# Humidorium.net
KiCad netlist of a schematic drawn in EAGLE
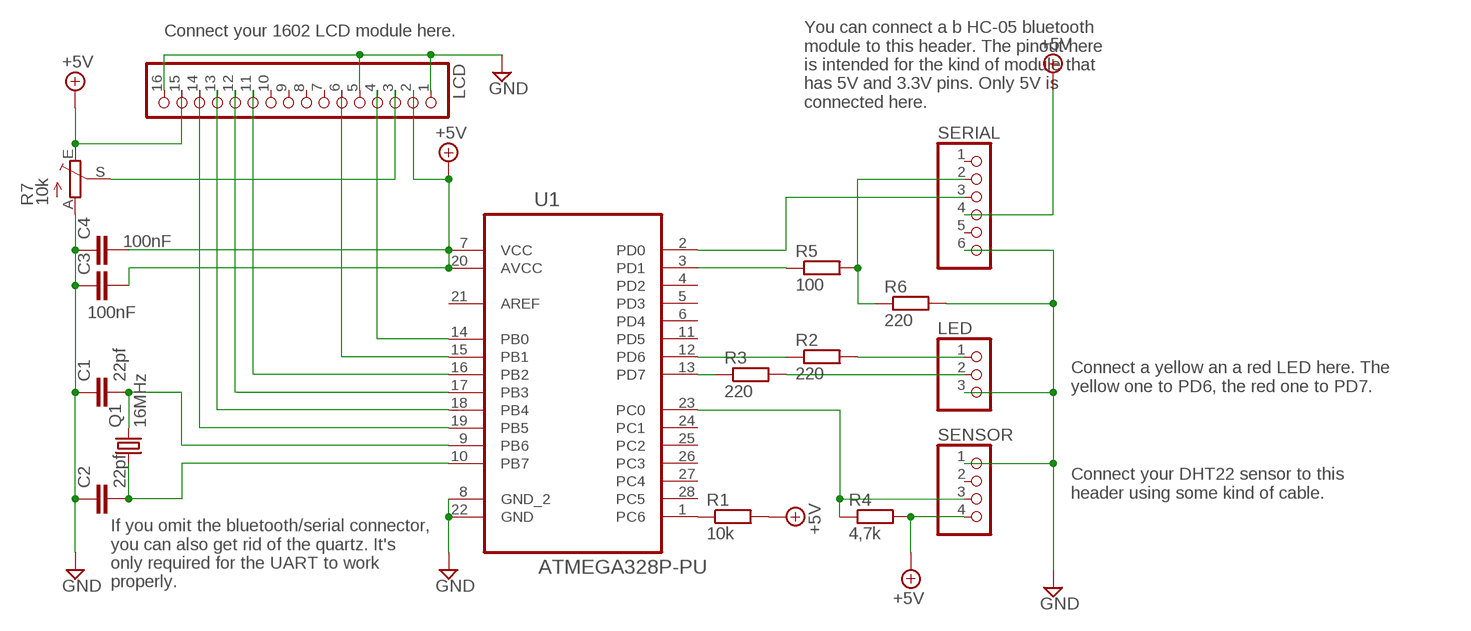
[diagram p0: schematic, sheet 1]

(export (version "E")
  (design (tool "Eeschema 10.0.6"))
  (components
    (comp (ref "C1")
      (value "22pf")
      (footprint "eagle-import:C025-024X044")
      (libsource (lib "eagle-import") (part "C-EU025-024X044"))
    )
    (comp (ref "C2")
      (value "22pf")
      (footprint "eagle-import:C025-024X044")
      (libsource (lib "eagle-import") (part "C-EU025-024X044"))
    )
    (comp (ref "C3")
      (value "100nF")
      (footprint "eagle-import:C025-024X044")
      (libsource (lib "eagle-import") (part "C-EU025-024X044"))
    )
    (comp (ref "C4")
      (value "100nF")
      (footprint "eagle-import:C025-024X044")
      (libsource (lib "eagle-import") (part "C-EU025-024X044"))
    )
    (comp (ref "LCD")
      (value "PINHD-1X16")
      (footprint "eagle-import:1X16")
      (libsource (lib "eagle-import") (part "PINHD-1X16"))
    )
    (comp (ref "LED")
      (value "PINHD-1X3")
      (footprint "eagle-import:1X03")
      (libsource (lib "eagle-import") (part "PINHD-1X3"))
    )
    (comp (ref "Q1")
      (value "16MHz")
      (footprint "eagle-import:HC33U-V")
      (libsource (lib "eagle-import") (part "CRYSTALHC33U-V"))
    )
    (comp (ref "R1")
      (value "10k")
      (footprint "eagle-import:0204V")
      (libsource (lib "eagle-import") (part "R-EU_0204/2V"))
    )
    (comp (ref "R2")
      (value "220")
      (footprint "eagle-import:0204_7")
      (libsource (lib "eagle-import") (part "R-EU_0204/7"))
    )
    (comp (ref "R3")
      (value "220")
      (footprint "eagle-import:0204_7")
      (libsource (lib "eagle-import") (part "R-EU_0204/7"))
    )
    (comp (ref "R4")
      (value "4,7k")
      (footprint "eagle-import:0204_7")
      (libsource (lib "eagle-import") (part "R-EU_0204/7"))
    )
    (comp (ref "R5")
      (value "100")
      (footprint "eagle-import:0204_7")
      (libsource (lib "eagle-import") (part "R-EU_0204/7"))
    )
    (comp (ref "R6")
      (value "220")
      (footprint "eagle-import:0204_7")
      (libsource (lib "eagle-import") (part "R-EU_0204/7"))
    )
    (comp (ref "R7")
      (value "10k")
      (footprint "eagle-import:B25P")
      (libsource (lib "eagle-import") (part "TRIM_EU-B25P"))
    )
    (comp (ref "SENSOR")
      (value "PINHD-1X4")
      (footprint "eagle-import:1X04")
      (libsource (lib "eagle-import") (part "PINHD-1X4"))
    )
    (comp (ref "SERIAL")
      (value "PINHD-1X6")
      (footprint "eagle-import:1X06")
      (libsource (lib "eagle-import") (part "PINHD-1X6"))
    )
    (comp (ref "U1")
      (value "ATMEGA328P-PU")
      (footprint "eagle-import:DIP254P762X457-28")
      (libsource (lib "eagle-import") (part "ATMEGA328P-PU"))
    )
  )
  (nets
    (net (code "1") (name "+5V") (class "Default")
      (node (ref "C3") (pin "2") (pinfunction "2_2") (pintype "passive"))
      (node (ref "C4") (pin "2") (pinfunction "2_2") (pintype "passive"))
      (node (ref "LCD") (pin "15") (pinfunction "15_15") (pintype "passive"))
      (node (ref "LCD") (pin "2") (pinfunction "2_2") (pintype "passive"))
      (node (ref "R1") (pin "2") (pinfunction "2_2") (pintype "passive"))
      (node (ref "R4") (pin "2") (pinfunction "2_2") (pintype "passive"))
      (node (ref "R7") (pin "E") (pinfunction "E_E") (pintype "passive"))
      (node (ref "SENSOR") (pin "4") (pinfunction "4_4") (pintype "passive"))
      (node (ref "SERIAL") (pin "4") (pinfunction "4_4") (pintype "passive"))
      (node (ref "U1") (pin "20") (pinfunction "AVCC_20") (pintype "power_in"))
      (node (ref "U1") (pin "7") (pinfunction "VCC_7") (pintype "power_in"))
    )
    (net (code "2") (name "GND") (class "Default")
      (node (ref "C1") (pin "1") (pinfunction "1_1") (pintype "passive"))
      (node (ref "C2") (pin "1") (pinfunction "1_1") (pintype "passive"))
      (node (ref "C3") (pin "1") (pinfunction "1_1") (pintype "passive"))
      (node (ref "C4") (pin "1") (pinfunction "1_1") (pintype "passive"))
      (node (ref "LCD") (pin "1") (pinfunction "1_1") (pintype "passive"))
      (node (ref "LCD") (pin "16") (pinfunction "16_16") (pintype "passive"))
      (node (ref "LCD") (pin "5") (pinfunction "5_5") (pintype "passive"))
      (node (ref "LED") (pin "3") (pinfunction "3_3") (pintype "passive"))
      (node (ref "R6") (pin "2") (pinfunction "2_2") (pintype "passive"))
      (node (ref "R7") (pin "A") (pinfunction "A_A") (pintype "passive"))
      (node (ref "SENSOR") (pin "1") (pinfunction "1_1") (pintype "passive"))
      (node (ref "SERIAL") (pin "6") (pinfunction "6_6") (pintype "passive"))
      (node (ref "U1") (pin "22") (pinfunction "GND_22") (pintype "passive"))
      (node (ref "U1") (pin "8") (pinfunction "GND_2_8") (pintype "passive"))
    )
    (net (code "3") (name "Net-(LCD-Pad3)") (class "Default")
      (node (ref "LCD") (pin "3") (pinfunction "3_3") (pintype "passive"))
      (node (ref "R7") (pin "S") (pinfunction "S_S") (pintype "passive"))
    )
    (net (code "4") (name "Net-(LED-Pad1)") (class "Default")
      (node (ref "LED") (pin "1") (pinfunction "1_1") (pintype "passive"))
      (node (ref "R2") (pin "2") (pinfunction "2_2") (pintype "passive"))
    )
    (net (code "5") (name "Net-(LED-Pad2)") (class "Default")
      (node (ref "LED") (pin "2") (pinfunction "2_2") (pintype "passive"))
      (node (ref "R3") (pin "2") (pinfunction "2_2") (pintype "passive"))
    )
    (net (code "6") (name "Net-(R5-Pad2)") (class "Default")
      (node (ref "R5") (pin "2") (pinfunction "2_2") (pintype "passive"))
      (node (ref "R6") (pin "1") (pinfunction "1_1") (pintype "passive"))
      (node (ref "SERIAL") (pin "2") (pinfunction "2_2") (pintype "passive"))
    )
    (net (code "7") (name "Net-(U1-PB0)") (class "Default")
      (node (ref "LCD") (pin "4") (pinfunction "4_4") (pintype "passive"))
      (node (ref "U1") (pin "14") (pinfunction "PB0_14") (pintype "bidirectional"))
    )
    (net (code "8") (name "Net-(U1-PB1)") (class "Default")
      (node (ref "LCD") (pin "6") (pinfunction "6_6") (pintype "passive"))
      (node (ref "U1") (pin "15") (pinfunction "PB1_15") (pintype "bidirectional"))
    )
    (net (code "9") (name "Net-(U1-PB2)") (class "Default")
      (node (ref "LCD") (pin "11") (pinfunction "11_11") (pintype "passive"))
      (node (ref "U1") (pin "16") (pinfunction "PB2_16") (pintype "bidirectional"))
    )
    (net (code "10") (name "Net-(U1-PB3)") (class "Default")
      (node (ref "LCD") (pin "12") (pinfunction "12_12") (pintype "passive"))
      (node (ref "U1") (pin "17") (pinfunction "PB3_17") (pintype "bidirectional"))
    )
    (net (code "11") (name "Net-(U1-PB4)") (class "Default")
      (node (ref "LCD") (pin "13") (pinfunction "13_13") (pintype "passive"))
      (node (ref "U1") (pin "18") (pinfunction "PB4_18") (pintype "bidirectional"))
    )
    (net (code "12") (name "Net-(U1-PB5)") (class "Default")
      (node (ref "LCD") (pin "14") (pinfunction "14_14") (pintype "passive"))
      (node (ref "U1") (pin "19") (pinfunction "PB5_19") (pintype "bidirectional"))
    )
    (net (code "13") (name "Net-(U1-PB6)") (class "Default")
      (node (ref "C1") (pin "2") (pinfunction "2_2") (pintype "passive"))
      (node (ref "Q1") (pin "2") (pinfunction "2_2") (pintype "passive"))
      (node (ref "U1") (pin "9") (pinfunction "PB6_9") (pintype "bidirectional"))
    )
    (net (code "14") (name "Net-(U1-PB7)") (class "Default")
      (node (ref "C2") (pin "2") (pinfunction "2_2") (pintype "passive"))
      (node (ref "Q1") (pin "1") (pinfunction "1_1") (pintype "passive"))
      (node (ref "U1") (pin "10") (pinfunction "PB7_10") (pintype "bidirectional"))
    )
    (net (code "15") (name "Net-(U1-PC0)") (class "Default")
      (node (ref "R4") (pin "1") (pinfunction "1_1") (pintype "passive"))
      (node (ref "SENSOR") (pin "3") (pinfunction "3_3") (pintype "passive"))
      (node (ref "U1") (pin "23") (pinfunction "PC0_23") (pintype "bidirectional"))
    )
    (net (code "16") (name "Net-(U1-PC6)") (class "Default")
      (node (ref "R1") (pin "1") (pinfunction "1_1") (pintype "passive"))
      (node (ref "U1") (pin "1") (pinfunction "PC6_1") (pintype "bidirectional"))
    )
    (net (code "17") (name "Net-(U1-PD0)") (class "Default")
      (node (ref "SERIAL") (pin "3") (pinfunction "3_3") (pintype "passive"))
      (node (ref "U1") (pin "2") (pinfunction "PD0_2") (pintype "bidirectional"))
    )
    (net (code "18") (name "Net-(U1-PD1)") (class "Default")
      (node (ref "R5") (pin "1") (pinfunction "1_1") (pintype "passive"))
      (node (ref "U1") (pin "3") (pinfunction "PD1_3") (pintype "bidirectional"))
    )
    (net (code "19") (name "Net-(U1-PD6)") (class "Default")
      (node (ref "R2") (pin "1") (pinfunction "1_1") (pintype "passive"))
      (node (ref "U1") (pin "12") (pinfunction "PD6_12") (pintype "bidirectional"))
    )
    (net (code "20") (name "Net-(U1-PD7)") (class "Default")
      (node (ref "R3") (pin "1") (pinfunction "1_1") (pintype "passive"))
      (node (ref "U1") (pin "13") (pinfunction "PD7_13") (pintype "bidirectional"))
    )
    (net (code "21") (name "unconnected-(LCD-Pad7)") (class "Default")
      (node (ref "LCD") (pin "7") (pinfunction "7_7") (pintype "passive"))
    )
    (net (code "22") (name "unconnected-(LCD-Pad8)") (class "Default")
      (node (ref "LCD") (pin "8") (pinfunction "8_8") (pintype "passive"))
    )
    (net (code "23") (name "unconnected-(LCD-Pad9)") (class "Default")
      (node (ref "LCD") (pin "9") (pinfunction "9_9") (pintype "passive"))
    )
    (net (code "24") (name "unconnected-(LCD-Pad10)") (class "Default")
      (node (ref "LCD") (pin "10") (pinfunction "10_10") (pintype "passive"))
    )
    (net (code "25") (name "unconnected-(SENSOR-Pad2)") (class "Default")
      (node (ref "SENSOR") (pin "2") (pinfunction "2_2") (pintype "passive"))
    )
    (net (code "26") (name "unconnected-(SERIAL-Pad1)") (class "Default")
      (node (ref "SERIAL") (pin "1") (pinfunction "1_1") (pintype "passive"))
    )
    (net (code "27") (name "unconnected-(SERIAL-Pad5)") (class "Default")
      (node (ref "SERIAL") (pin "5") (pinfunction "5_5") (pintype "passive"))
    )
    (net (code "28") (name "unconnected-(U1-AREF-Pad21)") (class "Default")
      (node (ref "U1") (pin "21") (pinfunction "AREF_21") (pintype "input"))
    )
    (net (code "29") (name "unconnected-(U1-PC1-Pad24)") (class "Default")
      (node (ref "U1") (pin "24") (pinfunction "PC1_24") (pintype "bidirectional"))
    )
    (net (code "30") (name "unconnected-(U1-PC2-Pad25)") (class "Default")
      (node (ref "U1") (pin "25") (pinfunction "PC2_25") (pintype "bidirectional"))
    )
    (net (code "31") (name "unconnected-(U1-PC3-Pad26)") (class "Default")
      (node (ref "U1") (pin "26") (pinfunction "PC3_26") (pintype "bidirectional"))
    )
    (net (code "32") (name "unconnected-(U1-PC4-Pad27)") (class "Default")
      (node (ref "U1") (pin "27") (pinfunction "PC4_27") (pintype "bidirectional"))
    )
    (net (code "33") (name "unconnected-(U1-PC5-Pad28)") (class "Default")
      (node (ref "U1") (pin "28") (pinfunction "PC5_28") (pintype "bidirectional"))
    )
    (net (code "34") (name "unconnected-(U1-PD2-Pad4)") (class "Default")
      (node (ref "U1") (pin "4") (pinfunction "PD2_4") (pintype "bidirectional"))
    )
    (net (code "35") (name "unconnected-(U1-PD3-Pad5)") (class "Default")
      (node (ref "U1") (pin "5") (pinfunction "PD3_5") (pintype "bidirectional"))
    )
    (net (code "36") (name "unconnected-(U1-PD4-Pad6)") (class "Default")
      (node (ref "U1") (pin "6") (pinfunction "PD4_6") (pintype "bidirectional"))
    )
    (net (code "37") (name "unconnected-(U1-PD5-Pad11)") (class "Default")
      (node (ref "U1") (pin "11") (pinfunction "PD5_11") (pintype "bidirectional"))
    )
  )
)
